# interface.net
KiCad netlist of a schematic drawn in Altium Designer
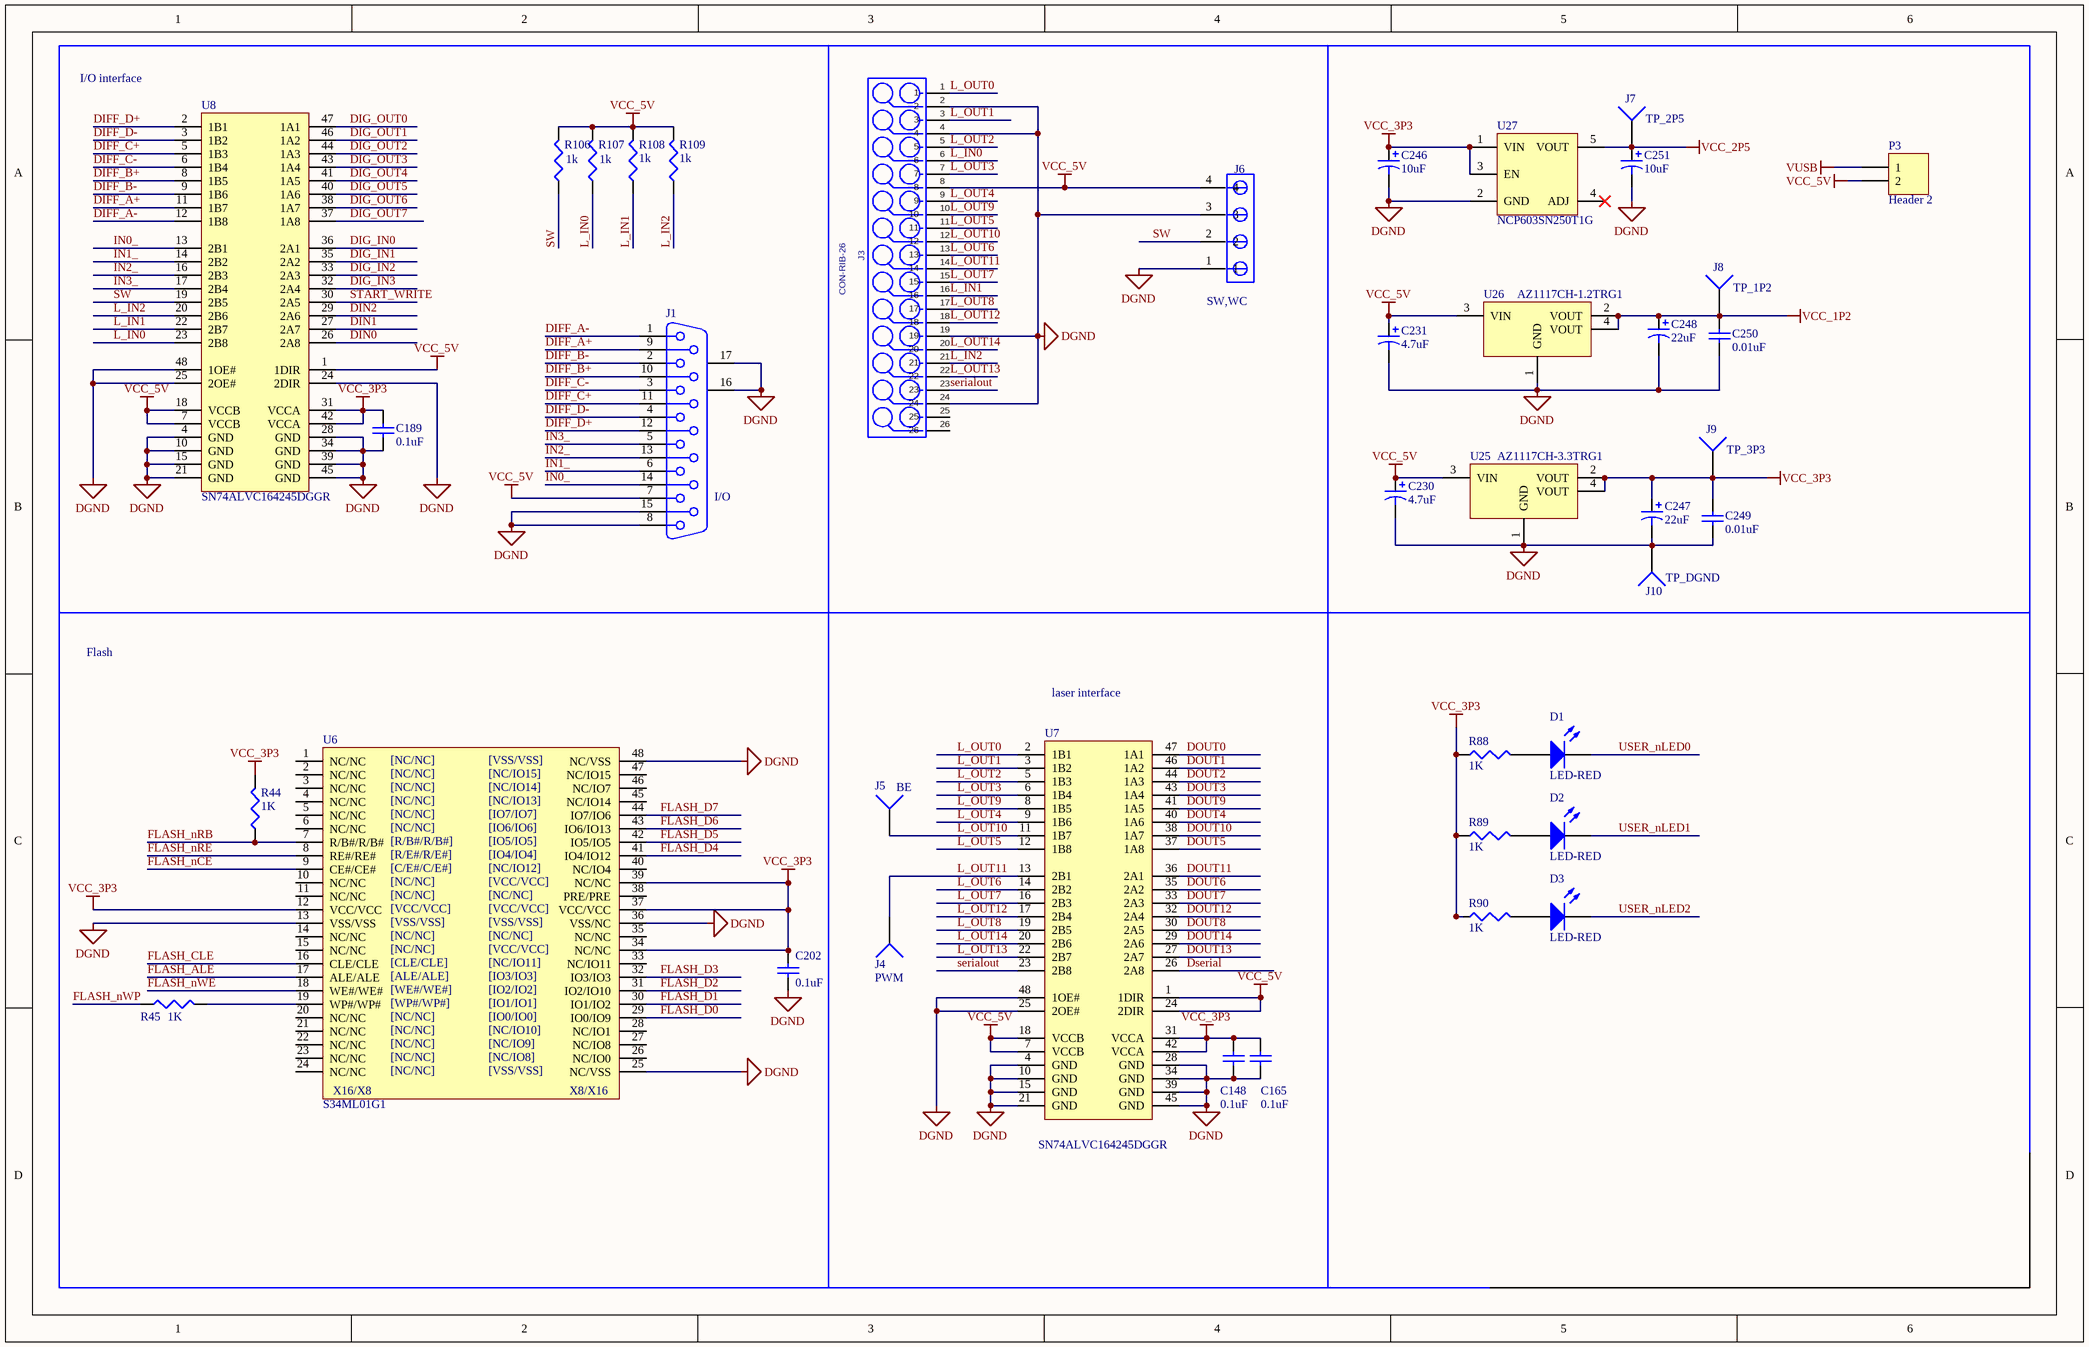
[diagram p0: interface.SchDoc]

(export (version "E")
  (design (tool "Eeschema 10.0.6"))
  (components
    (comp (ref "C148")
      (value "0.1uF")
      (footprint "C_0402")
      (description "Capacitor (Semiconductor SIM Model)")
      (fields (field (name "Comment") "Capacitor") (field (name "PUBLISHER") "Altium Limited"))
      (libsource (lib "Miscellaneous Devices") (part "Cap Semi"))
    )
    (comp (ref "C165")
      (value "0.1uF")
      (footprint "C_0402")
      (description "Capacitor (Semiconductor SIM Model)")
      (fields (field (name "Comment") "Capacitor") (field (name "PUBLISHER") "Altium Limited"))
      (libsource (lib "Miscellaneous Devices") (part "Cap Semi"))
    )
    (comp (ref "C189")
      (value "0.1uF")
      (footprint "C_0402")
      (description "Capacitor (Semiconductor SIM Model)")
      (fields (field (name "Comment") "Capacitor") (field (name "PUBLISHER") "Altium Limited"))
      (libsource (lib "Miscellaneous Devices") (part "Cap Semi"))
    )
    (comp (ref "C202")
      (value "0.1uF")
      (footprint "C_0402")
      (description "Capacitor (Semiconductor SIM Model)")
      (fields (field (name "Comment") "Capacitor") (field (name "PUBLISHER") "Altium Limited"))
      (libsource (lib "Miscellaneous Devices") (part "Cap Semi"))
    )
    (comp (ref "C230")
      (value "4.7uF")
      (footprint "CAP_B")
      (description "Polarized Capacitor (Surface Mount)")
      (fields (field (name "Comment") "Polarized Capacitor") (field (name "PUBLISHER") "Altium Limited"))
      (libsource (lib "Miscellaneous Devices") (part "Cap Pol3"))
    )
    (comp (ref "C231")
      (value "4.7uF")
      (footprint "CAP_B")
      (description "Polarized Capacitor (Surface Mount)")
      (fields (field (name "Comment") "Polarized Capacitor") (field (name "PUBLISHER") "Altium Limited"))
      (libsource (lib "Miscellaneous Devices") (part "Cap Pol3"))
    )
    (comp (ref "C246")
      (value "10uF")
      (footprint "CAP_B")
      (description "Polarized Capacitor (Surface Mount)")
      (fields (field (name "Comment") "Polarized Capacitor") (field (name "PUBLISHER") "Altium Limited"))
      (libsource (lib "Miscellaneous Devices") (part "Cap Pol3"))
    )
    (comp (ref "C247")
      (value "22uF")
      (footprint "CAP_B")
      (description "Polarized Capacitor (Surface Mount)")
      (fields (field (name "Comment") "Polarized Capacitor") (field (name "PUBLISHER") "Altium Limited"))
      (libsource (lib "Miscellaneous Devices") (part "Cap Pol3"))
    )
    (comp (ref "C248")
      (value "22uF")
      (footprint "CAP_B")
      (description "Polarized Capacitor (Surface Mount)")
      (fields (field (name "Comment") "Polarized Capacitor") (field (name "PUBLISHER") "Altium Limited"))
      (libsource (lib "Miscellaneous Devices") (part "Cap Pol3"))
    )
    (comp (ref "C249")
      (value "0.01uF")
      (footprint "C_0402")
      (description "Capacitor (Semiconductor SIM Model)")
      (fields (field (name "Comment") "Capacitor") (field (name "PUBLISHER") "Altium Limited"))
      (libsource (lib "Miscellaneous Devices") (part "Cap Semi"))
    )
    (comp (ref "C250")
      (value "0.01uF")
      (footprint "C_0402")
      (description "Capacitor (Semiconductor SIM Model)")
      (fields (field (name "Comment") "Capacitor") (field (name "PUBLISHER") "Altium Limited"))
      (libsource (lib "Miscellaneous Devices") (part "Cap Semi"))
    )
    (comp (ref "C251")
      (value "10uF")
      (footprint "CAP_B")
      (description "Polarized Capacitor (Surface Mount)")
      (fields (field (name "Comment") "Polarized Capacitor") (field (name "PUBLISHER") "Altium Limited"))
      (libsource (lib "Miscellaneous Devices") (part "Cap Pol3"))
    )
    (comp (ref "D1")
      (value "LED-RED")
      (footprint "3.2X1.6X1.1")
      (description "Typical RED, GREEN, YELLOW, AMBER GaAs LED")
      (fields (field (name "PUBLISHER") "Altium Limited"))
      (libsource (lib "Miscellaneous Devices") (part "LED2"))
    )
    (comp (ref "D2")
      (value "LED-RED")
      (footprint "3.2X1.6X1.1")
      (description "Typical RED, GREEN, YELLOW, AMBER GaAs LED")
      (fields (field (name "PUBLISHER") "Altium Limited"))
      (libsource (lib "Miscellaneous Devices") (part "LED2"))
    )
    (comp (ref "D3")
      (value "LED-RED")
      (footprint "3.2X1.6X1.1")
      (description "Typical RED, GREEN, YELLOW, AMBER GaAs LED")
      (fields (field (name "PUBLISHER") "Altium Limited"))
      (libsource (lib "Miscellaneous Devices") (part "LED2"))
    )
    (comp (ref "J1")
      (value "I/O")
      (footprint "DB15")
      (description "Receptacle Assembly, 15 Position, Right Angle")
      (fields (field (name "PUBLISHER") "Altium Limited"))
      (libsource (lib "hardcore control board") (part "D Connector 15"))
    )
    (comp (ref "J3")
      (value "CON-RIB-26")
      (footprint "H26-2P54-DIP")
      (description "CONN HEADER 26POS DUAL VERT PCB")
      (libsource (lib "*") (part "CON-RIB-26"))
    )
    (comp (ref "J4")
      (value "PWM")
      (footprint "1PAD")
      (description "Socket")
      (fields (field (name "PUBLISHER") "Altium Limited"))
      (libsource (lib "Miscellaneous Connectors") (part "Socket"))
    )
    (comp (ref "J5")
      (value "BE")
      (footprint "1PAD")
      (description "Socket")
      (fields (field (name "PUBLISHER") "Altium Limited"))
      (libsource (lib "Miscellaneous Connectors") (part "Socket"))
    )
    (comp (ref "J6")
      (value "SW,WC")
      (footprint "2510-4P")
      (fields (field (name "SPIL PART #") "70543-0003") (field (name "Comment") "SIP-4P-100"))
      (libsource (lib "PCB_Project_1") (part "HEADER_4"))
    )
    (comp (ref "J7")
      (value "TP_2P5")
      (footprint "1PAD")
      (description "Socket")
      (fields (field (name "PUBLISHER") "Altium Limited"))
      (libsource (lib "Miscellaneous Connectors") (part "Socket"))
    )
    (comp (ref "J8")
      (value "TP_1P2")
      (footprint "1PAD")
      (description "Socket")
      (fields (field (name "PUBLISHER") "Altium Limited"))
      (libsource (lib "Miscellaneous Connectors") (part "Socket"))
    )
    (comp (ref "J9")
      (value "TP_3P3")
      (footprint "1PAD")
      (description "Socket")
      (fields (field (name "PUBLISHER") "Altium Limited"))
      (libsource (lib "Miscellaneous Connectors") (part "Socket"))
    )
    (comp (ref "J10")
      (value "TP_DGND")
      (footprint "1PAD")
      (description "Socket")
      (fields (field (name "PUBLISHER") "Altium Limited"))
      (libsource (lib "Miscellaneous Connectors") (part "Socket"))
    )
    (comp (ref "P3")
      (value "Header 2")
      (footprint "HDR1X2")
      (description "Header, 2-Pin")
      (fields (field (name "PUBLISHER") "Altium Limited"))
      (libsource (lib "Miscellaneous Connectors") (part "Header 2"))
    )
    (comp (ref "R44")
      (value "1K")
      (footprint "J1-0603")
      (description "Resistor")
      (fields (field (name "PUBLISHER") "Altium Limited"))
      (libsource (lib "Miscellaneous Devices") (part "Res3"))
    )
    (comp (ref "R45")
      (value "1K")
      (footprint "J1-0603")
      (description "Resistor")
      (fields (field (name "PUBLISHER") "Altium Limited"))
      (libsource (lib "Miscellaneous Devices") (part "Res3"))
    )
    (comp (ref "R88")
      (value "1K")
      (footprint "J1-0603")
      (description "Resistor")
      (fields (field (name "PUBLISHER") "Altium Limited"))
      (libsource (lib "Miscellaneous Devices") (part "Res3"))
    )
    (comp (ref "R89")
      (value "1K")
      (footprint "J1-0603")
      (description "Resistor")
      (fields (field (name "PUBLISHER") "Altium Limited"))
      (libsource (lib "Miscellaneous Devices") (part "Res3"))
    )
    (comp (ref "R90")
      (value "1K")
      (footprint "J1-0603")
      (description "Resistor")
      (fields (field (name "PUBLISHER") "Altium Limited"))
      (libsource (lib "Miscellaneous Devices") (part "Res3"))
    )
    (comp (ref "R106")
      (value "1k")
      (footprint "J1-0603")
      (description "Resistor")
      (fields (field (name "PUBLISHER") "Altium Limited"))
      (libsource (lib "Miscellaneous Devices") (part "Res3"))
    )
    (comp (ref "R107")
      (value "1k")
      (footprint "J1-0603")
      (description "Resistor")
      (fields (field (name "PUBLISHER") "Altium Limited"))
      (libsource (lib "Miscellaneous Devices") (part "Res3"))
    )
    (comp (ref "R108")
      (value "1k")
      (footprint "J1-0603")
      (description "Resistor")
      (fields (field (name "PUBLISHER") "Altium Limited"))
      (libsource (lib "Miscellaneous Devices") (part "Res3"))
    )
    (comp (ref "R109")
      (value "1k")
      (footprint "J1-0603")
      (description "Resistor")
      (fields (field (name "PUBLISHER") "Altium Limited"))
      (libsource (lib "Miscellaneous Devices") (part "Res3"))
    )
    (comp (ref "U6")
      (value "S34ML01G1")
      (footprint "TSOP48")
      (description "NAND Flash")
      (libsource (lib "schlib_clc") (part "K9F1GXXU0M"))
    )
    (comp (ref "U7")
      (value "SN74ALVC164245DGGR")
      (footprint "TSSOP48_N")
      (description "Transceiver With 3-  State Outputs")
      (libsource (lib "clc_ad_pro") (part "SN74ALVC164245"))
    )
    (comp (ref "U8")
      (value "SN74ALVC164245DGGR")
      (footprint "TSSOP48_N")
      (description "Transceiver With 3-  State Outputs")
      (libsource (lib "clc_ad_pro") (part "SN74ALVC164245"))
    )
    (comp (ref "U25")
      (value "AZ1117CH-3.3TRG1")
      (footprint "SOT223_N")
      (libsource (lib "PCB_Project") (part "VR3.3V"))
    )
    (comp (ref "U26")
      (value "AZ1117CH-1.2TRG1")
      (footprint "SOT223_N")
      (libsource (lib "PCB_Project") (part "VR3.3V"))
    )
    (comp (ref "U27")
      (value "NCP603SN250T1G")
      (footprint "TSOP_5")
      (description "CMOS LDO Regulator")
      (libsource (lib "apex_usb_v2") (part "NCP603SN"))
    )
  )
  (nets
    (net (code "1") (name "/DIFF_A+") (class "Default")
      (node (ref "J1") (pin "9") (pinfunction "9_9") (pintype "passive"))
      (node (ref "U8") (pin "11") (pinfunction "1B7_11") (pintype "passive"))
    )
    (net (code "2") (name "/DIFF_A-") (class "Default")
      (node (ref "J1") (pin "1") (pinfunction "1_1") (pintype "passive"))
      (node (ref "U8") (pin "12") (pinfunction "1B8_12") (pintype "passive"))
    )
    (net (code "3") (name "/DIFF_B+") (class "Default")
      (node (ref "J1") (pin "10") (pinfunction "10_10") (pintype "passive"))
      (node (ref "U8") (pin "8") (pinfunction "1B5_8") (pintype "passive"))
    )
    (net (code "4") (name "/DIFF_B-") (class "Default")
      (node (ref "J1") (pin "2") (pinfunction "2_2") (pintype "passive"))
      (node (ref "U8") (pin "9") (pinfunction "1B6_9") (pintype "passive"))
    )
    (net (code "5") (name "/DIFF_C+") (class "Default")
      (node (ref "J1") (pin "11") (pinfunction "11_11") (pintype "passive"))
      (node (ref "U8") (pin "5") (pinfunction "1B3_5") (pintype "passive"))
    )
    (net (code "6") (name "/DIFF_C-") (class "Default")
      (node (ref "J1") (pin "3") (pinfunction "3_3") (pintype "passive"))
      (node (ref "U8") (pin "6") (pinfunction "1B4_6") (pintype "passive"))
    )
    (net (code "7") (name "/DIFF_D+") (class "Default")
      (node (ref "J1") (pin "12") (pinfunction "12_12") (pintype "passive"))
      (node (ref "U8") (pin "2") (pinfunction "1B1_2") (pintype "passive"))
    )
    (net (code "8") (name "/DIFF_D-") (class "Default")
      (node (ref "J1") (pin "4") (pinfunction "4_4") (pintype "passive"))
      (node (ref "U8") (pin "3") (pinfunction "1B2_3") (pintype "passive"))
    )
    (net (code "9") (name "/DIG_IN0") (class "Default")
      (node (ref "U8") (pin "36") (pinfunction "2A1_36") (pintype "passive"))
    )
    (net (code "10") (name "/DIG_IN1") (class "Default")
      (node (ref "U8") (pin "35") (pinfunction "2A2_35") (pintype "passive"))
    )
    (net (code "11") (name "/DIG_IN2") (class "Default")
      (node (ref "U8") (pin "33") (pinfunction "2A3_33") (pintype "passive"))
    )
    (net (code "12") (name "/DIG_IN3") (class "Default")
      (node (ref "U8") (pin "32") (pinfunction "2A4_32") (pintype "passive"))
    )
    (net (code "13") (name "/DIG_OUT0") (class "Default")
      (node (ref "U8") (pin "47") (pinfunction "1A1_47") (pintype "passive"))
    )
    (net (code "14") (name "/DIG_OUT1") (class "Default")
      (node (ref "U8") (pin "46") (pinfunction "1A2_46") (pintype "passive"))
    )
    (net (code "15") (name "/DIG_OUT2") (class "Default")
      (node (ref "U8") (pin "44") (pinfunction "1A3_44") (pintype "passive"))
    )
    (net (code "16") (name "/DIG_OUT3") (class "Default")
      (node (ref "U8") (pin "43") (pinfunction "1A4_43") (pintype "passive"))
    )
    (net (code "17") (name "/DIG_OUT4") (class "Default")
      (node (ref "U8") (pin "41") (pinfunction "1A5_41") (pintype "passive"))
    )
    (net (code "18") (name "/DIG_OUT5") (class "Default")
      (node (ref "U8") (pin "40") (pinfunction "1A6_40") (pintype "passive"))
    )
    (net (code "19") (name "/DIG_OUT6") (class "Default")
      (node (ref "U8") (pin "38") (pinfunction "1A7_38") (pintype "passive"))
    )
    (net (code "20") (name "/DIG_OUT7") (class "Default")
      (node (ref "U8") (pin "37") (pinfunction "1A8_37") (pintype "passive"))
    )
    (net (code "21") (name "/DIN0") (class "Default")
      (node (ref "U8") (pin "26") (pinfunction "2A8_26") (pintype "passive"))
    )
    (net (code "22") (name "/DIN1") (class "Default")
      (node (ref "U8") (pin "27") (pinfunction "2A7_27") (pintype "passive"))
    )
    (net (code "23") (name "/DIN2") (class "Default")
      (node (ref "U8") (pin "29") (pinfunction "2A6_29") (pintype "passive"))
    )
    (net (code "24") (name "/DOUT0") (class "Default")
      (node (ref "U7") (pin "47") (pinfunction "1A1_47") (pintype "passive"))
    )
    (net (code "25") (name "/DOUT1") (class "Default")
      (node (ref "U7") (pin "46") (pinfunction "1A2_46") (pintype "passive"))
    )
    (net (code "26") (name "/DOUT2") (class "Default")
      (node (ref "U7") (pin "44") (pinfunction "1A3_44") (pintype "passive"))
    )
    (net (code "27") (name "/DOUT3") (class "Default")
      (node (ref "U7") (pin "43") (pinfunction "1A4_43") (pintype "passive"))
    )
    (net (code "28") (name "/DOUT4") (class "Default")
      (node (ref "U7") (pin "40") (pinfunction "1A6_40") (pintype "passive"))
    )
    (net (code "29") (name "/DOUT5") (class "Default")
      (node (ref "U7") (pin "37") (pinfunction "1A8_37") (pintype "passive"))
    )
    (net (code "30") (name "/DOUT6") (class "Default")
      (node (ref "U7") (pin "35") (pinfunction "2A2_35") (pintype "passive"))
    )
    (net (code "31") (name "/DOUT7") (class "Default")
      (node (ref "U7") (pin "33") (pinfunction "2A3_33") (pintype "passive"))
    )
    (net (code "32") (name "/DOUT8") (class "Default")
      (node (ref "U7") (pin "30") (pinfunction "2A5_30") (pintype "passive"))
    )
    (net (code "33") (name "/DOUT9") (class "Default")
      (node (ref "U7") (pin "41") (pinfunction "1A5_41") (pintype "passive"))
    )
    (net (code "34") (name "/DOUT10") (class "Default")
      (node (ref "U7") (pin "38") (pinfunction "1A7_38") (pintype "passive"))
    )
    (net (code "35") (name "/DOUT11") (class "Default")
      (node (ref "U7") (pin "36") (pinfunction "2A1_36") (pintype "passive"))
    )
    (net (code "36") (name "/DOUT12") (class "Default")
      (node (ref "U7") (pin "32") (pinfunction "2A4_32") (pintype "passive"))
    )
    (net (code "37") (name "/DOUT13") (class "Default")
      (node (ref "U7") (pin "27") (pinfunction "2A7_27") (pintype "passive"))
    )
    (net (code "38") (name "/DOUT14") (class "Default")
      (node (ref "U7") (pin "29") (pinfunction "2A6_29") (pintype "passive"))
    )
    (net (code "39") (name "/Dserial") (class "Default")
      (node (ref "U7") (pin "26") (pinfunction "2A8_26") (pintype "passive"))
    )
    (net (code "40") (name "/FLASH_ALE") (class "Default")
      (node (ref "U6") (pin "17") (pinfunction "ALE/ALE_17") (pintype "passive"))
    )
    (net (code "41") (name "/FLASH_CLE") (class "Default")
      (node (ref "U6") (pin "16") (pinfunction "CLE/CLE_16") (pintype "passive"))
    )
    (net (code "42") (name "/FLASH_D0") (class "Default")
      (node (ref "U6") (pin "29") (pinfunction "IO0/IO9_29") (pintype "passive"))
    )
    (net (code "43") (name "/FLASH_D1") (class "Default")
      (node (ref "U6") (pin "30") (pinfunction "IO1/IO2_30") (pintype "passive"))
    )
    (net (code "44") (name "/FLASH_D2") (class "Default")
      (node (ref "U6") (pin "31") (pinfunction "IO2/IO10_31") (pintype "passive"))
    )
    (net (code "45") (name "/FLASH_D3") (class "Default")
      (node (ref "U6") (pin "32") (pinfunction "IO3/IO3_32") (pintype "passive"))
    )
    (net (code "46") (name "/FLASH_D4") (class "Default")
      (node (ref "U6") (pin "41") (pinfunction "IO4/IO12_41") (pintype "passive"))
    )
    (net (code "47") (name "/FLASH_D5") (class "Default")
      (node (ref "U6") (pin "42") (pinfunction "IO5/IO5_42") (pintype "passive"))
    )
    (net (code "48") (name "/FLASH_D6") (class "Default")
      (node (ref "U6") (pin "43") (pinfunction "IO6/IO13_43") (pintype "passive"))
    )
    (net (code "49") (name "/FLASH_D7") (class "Default")
      (node (ref "U6") (pin "44") (pinfunction "IO7/IO6_44") (pintype "passive"))
    )
    (net (code "50") (name "/FLASH_nCE") (class "Default")
      (node (ref "U6") (pin "9") (pinfunction "CE#/CE#_9") (pintype "passive"))
    )
    (net (code "51") (name "/FLASH_nRB") (class "Default")
      (node (ref "R44") (pin "1") (pinfunction "1_1") (pintype "passive"))
      (node (ref "U6") (pin "7") (pinfunction "R/B#/R/B#_7") (pintype "passive"))
    )
    (net (code "52") (name "/FLASH_nRE") (class "Default")
      (node (ref "U6") (pin "8") (pinfunction "RE#/RE#_8") (pintype "passive"))
    )
    (net (code "53") (name "/FLASH_nWE") (class "Default")
      (node (ref "U6") (pin "18") (pinfunction "WE#/WE#_18") (pintype "passive"))
    )
    (net (code "54") (name "/FLASH_nWP") (class "Default")
      (node (ref "R45") (pin "1") (pinfunction "1_1") (pintype "passive"))
    )
    (net (code "55") (name "/IN0_") (class "Default")
      (node (ref "J1") (pin "14") (pinfunction "14_14") (pintype "passive"))
      (node (ref "U8") (pin "13") (pinfunction "2B1_13") (pintype "passive"))
    )
    (net (code "56") (name "/IN1_") (class "Default")
      (node (ref "J1") (pin "6") (pinfunction "6_6") (pintype "passive"))
      (node (ref "U8") (pin "14") (pinfunction "2B2_14") (pintype "passive"))
    )
    (net (code "57") (name "/IN2_") (class "Default")
      (node (ref "J1") (pin "13") (pinfunction "13_13") (pintype "passive"))
      (node (ref "U8") (pin "16") (pinfunction "2B3_16") (pintype "passive"))
    )
    (net (code "58") (name "/IN3_") (class "Default")
      (node (ref "J1") (pin "5") (pinfunction "5_5") (pintype "passive"))
      (node (ref "U8") (pin "17") (pinfunction "2B4_17") (pintype "passive"))
    )
    (net (code "59") (name "/L_IN0") (class "Default")
      (node (ref "J3") (pin "6") (pinfunction "6_6") (pintype "passive"))
      (node (ref "R107") (pin "1") (pinfunction "1_1") (pintype "passive"))
      (node (ref "U8") (pin "23") (pinfunction "2B8_23") (pintype "passive"))
    )
    (net (code "60") (name "/L_IN1") (class "Default")
      (node (ref "J3") (pin "16") (pinfunction "16_16") (pintype "passive"))
      (node (ref "R108") (pin "1") (pinfunction "1_1") (pintype "passive"))
      (node (ref "U8") (pin "22") (pinfunction "2B7_22") (pintype "passive"))
    )
    (net (code "61") (name "/L_IN2") (class "Default")
      (node (ref "J3") (pin "21") (pinfunction "21_21") (pintype "passive"))
      (node (ref "R109") (pin "1") (pinfunction "1_1") (pintype "passive"))
      (node (ref "U8") (pin "20") (pinfunction "2B6_20") (pintype "passive"))
    )
    (net (code "62") (name "/L_OUT0") (class "Default")
      (node (ref "J3") (pin "1") (pinfunction "1_1") (pintype "passive"))
      (node (ref "U7") (pin "2") (pinfunction "1B1_2") (pintype "passive"))
    )
    (net (code "63") (name "/L_OUT1") (class "Default")
      (node (ref "J3") (pin "3") (pinfunction "3_3") (pintype "passive"))
      (node (ref "U7") (pin "3") (pinfunction "1B2_3") (pintype "passive"))
    )
    (net (code "64") (name "/L_OUT2") (class "Default")
      (node (ref "J3") (pin "5") (pinfunction "5_5") (pintype "passive"))
      (node (ref "U7") (pin "5") (pinfunction "1B3_5") (pintype "passive"))
    )
    (net (code "65") (name "/L_OUT3") (class "Default")
      (node (ref "J3") (pin "7") (pinfunction "7_7") (pintype "passive"))
      (node (ref "U7") (pin "6") (pinfunction "1B4_6") (pintype "passive"))
    )
    (net (code "66") (name "/L_OUT4") (class "Default")
      (node (ref "J3") (pin "9") (pinfunction "9_9") (pintype "passive"))
      (node (ref "U7") (pin "9") (pinfunction "1B6_9") (pintype "passive"))
    )
    (net (code "67") (name "/L_OUT5") (class "Default")
      (node (ref "J3") (pin "11") (pinfunction "11_11") (pintype "passive"))
      (node (ref "U7") (pin "12") (pinfunction "1B8_12") (pintype "passive"))
    )
    (net (code "68") (name "/L_OUT6") (class "Default")
      (node (ref "J3") (pin "13") (pinfunction "13_13") (pintype "passive"))
      (node (ref "U7") (pin "14") (pinfunction "2B2_14") (pintype "passive"))
    )
    (net (code "69") (name "/L_OUT7") (class "Default")
      (node (ref "J3") (pin "15") (pinfunction "15_15") (pintype "passive"))
      (node (ref "U7") (pin "16") (pinfunction "2B3_16") (pintype "passive"))
    )
    (net (code "70") (name "/L_OUT8") (class "Default")
      (node (ref "J3") (pin "17") (pinfunction "17_17") (pintype "passive"))
      (node (ref "U7") (pin "19") (pinfunction "2B5_19") (pintype "passive"))
    )
    (net (code "71") (name "/L_OUT9") (class "Default")
      (node (ref "J3") (pin "10") (pinfunction "10_10") (pintype "passive"))
      (node (ref "U7") (pin "8") (pinfunction "1B5_8") (pintype "passive"))
    )
    (net (code "72") (name "/L_OUT10") (class "Default")
      (node (ref "J3") (pin "12") (pinfunction "12_12") (pintype "passive"))
      (node (ref "J5") (pin "1") (pinfunction "1_1") (pintype "passive"))
      (node (ref "U7") (pin "11") (pinfunction "1B7_11") (pintype "passive"))
    )
    (net (code "73") (name "/L_OUT11") (class "Default")
      (node (ref "J3") (pin "14") (pinfunction "14_14") (pintype "passive"))
      (node (ref "J4") (pin "1") (pinfunction "1_1") (pintype "passive"))
      (node (ref "U7") (pin "13") (pinfunction "2B1_13") (pintype "passive"))
    )
    (net (code "74") (name "/L_OUT12") (class "Default")
      (node (ref "J3") (pin "18") (pinfunction "18_18") (pintype "passive"))
      (node (ref "U7") (pin "17") (pinfunction "2B4_17") (pintype "passive"))
    )
    (net (code "75") (name "/L_OUT13") (class "Default")
      (node (ref "J3") (pin "22") (pinfunction "22_22") (pintype "passive"))
      (node (ref "U7") (pin "22") (pinfunction "2B7_22") (pintype "passive"))
    )
    (net (code "76") (name "/L_OUT14") (class "Default")
      (node (ref "J3") (pin "20") (pinfunction "20_20") (pintype "passive"))
      (node (ref "U7") (pin "20") (pinfunction "2B6_20") (pintype "passive"))
    )
    (net (code "77") (name "/START_WRITE") (class "Default")
      (node (ref "U8") (pin "30") (pinfunction "2A5_30") (pintype "passive"))
    )
    (net (code "78") (name "/SW") (class "Default")
      (node (ref "J6") (pin "2") (pinfunction "2_2") (pintype "passive"))
      (node (ref "R106") (pin "1") (pinfunction "1_1") (pintype "passive"))
      (node (ref "U8") (pin "19") (pinfunction "2B5_19") (pintype "passive"))
    )
    (net (code "79") (name "/USER_nLED0") (class "Default")
      (node (ref "D1") (pin "2") (pinfunction "K_2") (pintype "passive"))
    )
    (net (code "80") (name "/USER_nLED1") (class "Default")
      (node (ref "D2") (pin "2") (pinfunction "K_2") (pintype "passive"))
    )
    (net (code "81") (name "/USER_nLED2") (class "Default")
      (node (ref "D3") (pin "2") (pinfunction "K_2") (pintype "passive"))
    )
    (net (code "82") (name "/serialout") (class "Default")
      (node (ref "J3") (pin "23") (pinfunction "23_23") (pintype "passive"))
      (node (ref "U7") (pin "23") (pinfunction "2B8_23") (pintype "passive"))
    )
    (net (code "83") (name "DGND") (class "Default")
      (node (ref "C148") (pin "2") (pinfunction "2_2") (pintype "passive"))
      (node (ref "C165") (pin "1") (pinfunction "1_1") (pintype "passive"))
      (node (ref "C189") (pin "1") (pinfunction "1_1") (pintype "passive"))
      (node (ref "C202") (pin "1") (pinfunction "1_1") (pintype "passive"))
      (node (ref "C230") (pin "2") (pinfunction "2_2") (pintype "passive"))
      (node (ref "C231") (pin "2") (pinfunction "2_2") (pintype "passive"))
      (node (ref "C246") (pin "2") (pinfunction "2_2") (pintype "passive"))
      (node (ref "C247") (pin "2") (pinfunction "2_2") (pintype "passive"))
      (node (ref "C248") (pin "2") (pinfunction "2_2") (pintype "passive"))
      (node (ref "C249") (pin "2") (pinfunction "2_2") (pintype "passive"))
      (node (ref "C250") (pin "2") (pinfunction "2_2") (pintype "passive"))
      (node (ref "C251") (pin "2") (pinfunction "2_2") (pintype "passive"))
      (node (ref "J1") (pin "15") (pinfunction "15_15") (pintype "passive"))
      (node (ref "J1") (pin "16") (pinfunction "MH1_16") (pintype "passive"))
      (node (ref "J1") (pin "17") (pinfunction "MH2_17") (pintype "passive"))
      (node (ref "J1") (pin "8") (pinfunction "8_8") (pintype "passive"))
      (node (ref "J10") (pin "1") (pinfunction "1_1") (pintype "passive"))
      (node (ref "J3") (pin "19") (pinfunction "19_19") (pintype "passive"))
      (node (ref "J3") (pin "2") (pinfunction "2_2") (pintype "passive"))
      (node (ref "J3") (pin "24") (pinfunction "24_24") (pintype "passive"))
      (node (ref "J3") (pin "4") (pinfunction "4_4") (pintype "passive"))
      (node (ref "J6") (pin "1") (pinfunction "1_1") (pintype "passive"))
      (node (ref "J6") (pin "3") (pinfunction "3_3") (pintype "passive"))
      (node (ref "U25") (pin "1") (pinfunction "GND_1") (pintype "passive"))
      (node (ref "U26") (pin "1") (pinfunction "GND_1") (pintype "passive"))
      (node (ref "U27") (pin "2") (pinfunction "GND_2") (pintype "passive"))
      (node (ref "U6") (pin "13") (pinfunction "VSS/VSS_13") (pintype "passive"))
      (node (ref "U6") (pin "25") (pinfunction "NC/VSS_25") (pintype "passive"))
      (node (ref "U6") (pin "36") (pinfunction "VSS/NC_36") (pintype "passive"))
      (node (ref "U6") (pin "48") (pinfunction "NC/VSS_48") (pintype "passive"))
      (node (ref "U7") (pin "10") (pinfunction "GND_10") (pintype "passive"))
      (node (ref "U7") (pin "15") (pinfunction "GND_15") (pintype "passive"))
      (node (ref "U7") (pin "21") (pinfunction "GND_21") (pintype "passive"))
      (node (ref "U7") (pin "25") (pinfunction "2OE#_25") (pintype "passive"))
      (node (ref "U7") (pin "28") (pinfunction "GND_28") (pintype "passive"))
      (node (ref "U7") (pin "34") (pinfunction "GND_34") (pintype "passive"))
      (node (ref "U7") (pin "39") (pinfunction "GND_39") (pintype "passive"))
      (node (ref "U7") (pin "4") (pinfunction "GND_4") (pintype "passive"))
      (node (ref "U7") (pin "45") (pinfunction "GND_45") (pintype "passive"))
      (node (ref "U7") (pin "48") (pinfunction "1OE#_48") (pintype "passive"))
      (node (ref "U8") (pin "10") (pinfunction "GND_10") (pintype "passive"))
      (node (ref "U8") (pin "15") (pinfunction "GND_15") (pintype "passive"))
      (node (ref "U8") (pin "21") (pinfunction "GND_21") (pintype "passive"))
      (node (ref "U8") (pin "24") (pinfunction "2DIR_24") (pintype "passive"))
      (node (ref "U8") (pin "25") (pinfunction "2OE#_25") (pintype "passive"))
      (node (ref "U8") (pin "28") (pinfunction "GND_28") (pintype "passive"))
      (node (ref "U8") (pin "34") (pinfunction "GND_34") (pintype "passive"))
      (node (ref "U8") (pin "39") (pinfunction "GND_39") (pintype "passive"))
      (node (ref "U8") (pin "4") (pinfunction "GND_4") (pintype "passive"))
      (node (ref "U8") (pin "45") (pinfunction "GND_45") (pintype "passive"))
      (node (ref "U8") (pin "48") (pinfunction "1OE#_48") (pintype "passive"))
    )
    (net (code "84") (name "Net-(D1-A)") (class "Default")
      (node (ref "D1") (pin "1") (pinfunction "A_1") (pintype "passive"))
      (node (ref "R88") (pin "2") (pinfunction "2_2") (pintype "passive"))
    )
    (net (code "85") (name "Net-(D2-A)") (class "Default")
      (node (ref "D2") (pin "1") (pinfunction "A_1") (pintype "passive"))
      (node (ref "R89") (pin "2") (pinfunction "2_2") (pintype "passive"))
    )
    (net (code "86") (name "Net-(D3-A)") (class "Default")
      (node (ref "D3") (pin "1") (pinfunction "A_1") (pintype "passive"))
      (node (ref "R90") (pin "2") (pinfunction "2_2") (pintype "passive"))
    )
    (net (code "87") (name "Net-(U6-WP#{slash}WP#)") (class "Default")
      (node (ref "R45") (pin "2") (pinfunction "2_2") (pintype "passive"))
      (node (ref "U6") (pin "19") (pinfunction "WP#/WP#_19") (pintype "passive"))
    )
    (net (code "88") (name "VCC_1P2") (class "Default")
      (node (ref "C248") (pin "1") (pinfunction "1_1") (pintype "passive"))
      (node (ref "C250") (pin "1") (pinfunction "1_1") (pintype "passive"))
      (node (ref "J8") (pin "1") (pinfunction "1_1") (pintype "passive"))
      (node (ref "U26") (pin "2") (pinfunction "VOUT_2") (pintype "passive"))
      (node (ref "U26") (pin "4") (pinfunction "VOUT_4") (pintype "passive"))
    )
    (net (code "89") (name "VCC_2P5") (class "Default")
      (node (ref "C251") (pin "1") (pinfunction "1_1") (pintype "passive"))
      (node (ref "J7") (pin "1") (pinfunction "1_1") (pintype "passive"))
      (node (ref "U27") (pin "5") (pinfunction "VOUT_5") (pintype "passive"))
    )
    (net (code "90") (name "VCC_3P3") (class "Default")
      (node (ref "C148") (pin "1") (pinfunction "1_1") (pintype "passive"))
      (node (ref "C165") (pin "2") (pinfunction "2_2") (pintype "passive"))
      (node (ref "C189") (pin "2") (pinfunction "2_2") (pintype "passive"))
      (node (ref "C202") (pin "2") (pinfunction "2_2") (pintype "passive"))
      (node (ref "C246") (pin "1") (pinfunction "1_1") (pintype "passive"))
      (node (ref "C247") (pin "1") (pinfunction "1_1") (pintype "passive"))
      (node (ref "C249") (pin "1") (pinfunction "1_1") (pintype "passive"))
      (node (ref "J9") (pin "1") (pinfunction "1_1") (pintype "passive"))
      (node (ref "R44") (pin "2") (pinfunction "2_2") (pintype "passive"))
      (node (ref "R88") (pin "1") (pinfunction "1_1") (pintype "passive"))
      (node (ref "R89") (pin "1") (pinfunction "1_1") (pintype "passive"))
      (node (ref "R90") (pin "1") (pinfunction "1_1") (pintype "passive"))
      (node (ref "U25") (pin "2") (pinfunction "VOUT_2") (pintype "passive"))
      (node (ref "U25") (pin "4") (pinfunction "VOUT_4") (pintype "passive"))
      (node (ref "U27") (pin "1") (pinfunction "VIN_1") (pintype "passive"))
      (node (ref "U27") (pin "3") (pinfunction "EN_3") (pintype "passive"))
      (node (ref "U6") (pin "12") (pinfunction "VCC/VCC_12") (pintype "passive"))
      (node (ref "U6") (pin "34") (pinfunction "NC/NC_34") (pintype "passive"))
      (node (ref "U6") (pin "37") (pinfunction "VCC/VCC_37") (pintype "passive"))
      (node (ref "U6") (pin "39") (pinfunction "NC/NC_39") (pintype "passive"))
      (node (ref "U7") (pin "31") (pinfunction "VCCA_31") (pintype "passive"))
      (node (ref "U7") (pin "42") (pinfunction "VCCA_42") (pintype "passive"))
      (node (ref "U8") (pin "31") (pinfunction "VCCA_31") (pintype "passive"))
      (node (ref "U8") (pin "42") (pinfunction "VCCA_42") (pintype "passive"))
    )
    (net (code "91") (name "VCC_5V") (class "Default")
      (node (ref "C230") (pin "1") (pinfunction "1_1") (pintype "passive"))
      (node (ref "C231") (pin "1") (pinfunction "1_1") (pintype "passive"))
      (node (ref "J1") (pin "7") (pinfunction "7_7") (pintype "passive"))
      (node (ref "J3") (pin "8") (pinfunction "8_8") (pintype "passive"))
      (node (ref "J6") (pin "4") (pinfunction "4_4") (pintype "passive"))
      (node (ref "P3") (pin "2") (pinfunction "2_2") (pintype "passive"))
      (node (ref "R106") (pin "2") (pinfunction "2_2") (pintype "passive"))
      (node (ref "R107") (pin "2") (pinfunction "2_2") (pintype "passive"))
      (node (ref "R108") (pin "2") (pinfunction "2_2") (pintype "passive"))
      (node (ref "R109") (pin "2") (pinfunction "2_2") (pintype "passive"))
      (node (ref "U25") (pin "3") (pinfunction "VIN_3") (pintype "passive"))
      (node (ref "U26") (pin "3") (pinfunction "VIN_3") (pintype "passive"))
      (node (ref "U7") (pin "1") (pinfunction "1DIR_1") (pintype "passive"))
      (node (ref "U7") (pin "18") (pinfunction "VCCB_18") (pintype "passive"))
      (node (ref "U7") (pin "24") (pinfunction "2DIR_24") (pintype "passive"))
      (node (ref "U7") (pin "7") (pinfunction "VCCB_7") (pintype "passive"))
      (node (ref "U8") (pin "1") (pinfunction "1DIR_1") (pintype "passive"))
      (node (ref "U8") (pin "18") (pinfunction "VCCB_18") (pintype "passive"))
      (node (ref "U8") (pin "7") (pinfunction "VCCB_7") (pintype "passive"))
    )
    (net (code "92") (name "VUSB") (class "Default")
      (node (ref "P3") (pin "1") (pinfunction "1_1") (pintype "passive"))
    )
    (net (code "93") (name "unconnected-(J3-Pad25)") (class "Default")
      (node (ref "J3") (pin "25") (pinfunction "25_25") (pintype "passive"))
    )
    (net (code "94") (name "unconnected-(J3-Pad26)") (class "Default")
      (node (ref "J3") (pin "26") (pinfunction "26_26") (pintype "passive"))
    )
    (net (code "95") (name "unconnected-(U6-NC{slash}IO0-Pad26)") (class "Default")
      (node (ref "U6") (pin "26") (pinfunction "NC/IO0_26") (pintype "passive"))
    )
    (net (code "96") (name "unconnected-(U6-NC{slash}IO1-Pad28)") (class "Default")
      (node (ref "U6") (pin "28") (pinfunction "NC/IO1_28") (pintype "passive"))
    )
    (net (code "97") (name "unconnected-(U6-NC{slash}IO4-Pad40)") (class "Default")
      (node (ref "U6") (pin "40") (pinfunction "NC/IO4_40") (pintype "passive"))
    )
    (net (code "98") (name "unconnected-(U6-NC{slash}IO7-Pad46)") (class "Default")
      (node (ref "U6") (pin "46") (pinfunction "NC/IO7_46") (pintype "passive"))
    )
    (net (code "99") (name "unconnected-(U6-NC{slash}IO8-Pad27)") (class "Default")
      (node (ref "U6") (pin "27") (pinfunction "NC/IO8_27") (pintype "passive"))
    )
    (net (code "100") (name "unconnected-(U6-NC{slash}IO11-Pad33)") (class "Default")
      (node (ref "U6") (pin "33") (pinfunction "NC/IO11_33") (pintype "passive"))
    )
    (net (code "101") (name "unconnected-(U6-NC{slash}IO14-Pad45)") (class "Default")
      (node (ref "U6") (pin "45") (pinfunction "NC/IO14_45") (pintype "passive"))
    )
    (net (code "102") (name "unconnected-(U6-NC{slash}IO15-Pad47)") (class "Default")
      (node (ref "U6") (pin "47") (pinfunction "NC/IO15_47") (pintype "passive"))
    )
    (net (code "103") (name "unconnected-(U6-NC{slash}NC-Pad1)") (class "Default")
      (node (ref "U6") (pin "1") (pinfunction "NC/NC_1") (pintype "passive"))
    )
    (net (code "104") (name "unconnected-(U6-NC{slash}NC-Pad2)") (class "Default")
      (node (ref "U6") (pin "2") (pinfunction "NC/NC_2") (pintype "passive"))
    )
    (net (code "105") (name "unconnected-(U6-NC{slash}NC-Pad3)") (class "Default")
      (node (ref "U6") (pin "3") (pinfunction "NC/NC_3") (pintype "passive"))
    )
    (net (code "106") (name "unconnected-(U6-NC{slash}NC-Pad4)") (class "Default")
      (node (ref "U6") (pin "4") (pinfunction "NC/NC_4") (pintype "passive"))
    )
    (net (code "107") (name "unconnected-(U6-NC{slash}NC-Pad5)") (class "Default")
      (node (ref "U6") (pin "5") (pinfunction "NC/NC_5") (pintype "passive"))
    )
    (net (code "108") (name "unconnected-(U6-NC{slash}NC-Pad6)") (class "Default")
      (node (ref "U6") (pin "6") (pinfunction "NC/NC_6") (pintype "passive"))
    )
    (net (code "109") (name "unconnected-(U6-NC{slash}NC-Pad10)") (class "Default")
      (node (ref "U6") (pin "10") (pinfunction "NC/NC_10") (pintype "passive"))
    )
    (net (code "110") (name "unconnected-(U6-NC{slash}NC-Pad11)") (class "Default")
      (node (ref "U6") (pin "11") (pinfunction "NC/NC_11") (pintype "passive"))
    )
    (net (code "111") (name "unconnected-(U6-NC{slash}NC-Pad14)") (class "Default")
      (node (ref "U6") (pin "14") (pinfunction "NC/NC_14") (pintype "passive"))
    )
    (net (code "112") (name "unconnected-(U6-NC{slash}NC-Pad15)") (class "Default")
      (node (ref "U6") (pin "15") (pinfunction "NC/NC_15") (pintype "passive"))
    )
    (net (code "113") (name "unconnected-(U6-NC{slash}NC-Pad20)") (class "Default")
      (node (ref "U6") (pin "20") (pinfunction "NC/NC_20") (pintype "passive"))
    )
    (net (code "114") (name "unconnected-(U6-NC{slash}NC-Pad21)") (class "Default")
      (node (ref "U6") (pin "21") (pinfunction "NC/NC_21") (pintype "passive"))
    )
    (net (code "115") (name "unconnected-(U6-NC{slash}NC-Pad22)") (class "Default")
      (node (ref "U6") (pin "22") (pinfunction "NC/NC_22") (pintype "passive"))
    )
    (net (code "116") (name "unconnected-(U6-NC{slash}NC-Pad23)") (class "Default")
      (node (ref "U6") (pin "23") (pinfunction "NC/NC_23") (pintype "passive"))
    )
    (net (code "117") (name "unconnected-(U6-NC{slash}NC-Pad24)") (class "Default")
      (node (ref "U6") (pin "24") (pinfunction "NC/NC_24") (pintype "passive"))
    )
    (net (code "118") (name "unconnected-(U6-NC{slash}NC-Pad35)") (class "Default")
      (node (ref "U6") (pin "35") (pinfunction "NC/NC_35") (pintype "passive"))
    )
    (net (code "119") (name "unconnected-(U6-PRE{slash}PRE-Pad38)") (class "Default")
      (node (ref "U6") (pin "38") (pinfunction "PRE/PRE_38") (pintype "passive"))
    )
    (net (code "120") (name "unconnected-(U27-ADJ-Pad4)") (class "Default")
      (node (ref "U27") (pin "4") (pinfunction "ADJ_4") (pintype "passive+no_connect"))
    )
  )
)
